# HumFlex3_lower.net
KiCad netlist of a schematic drawn in Altium Designer
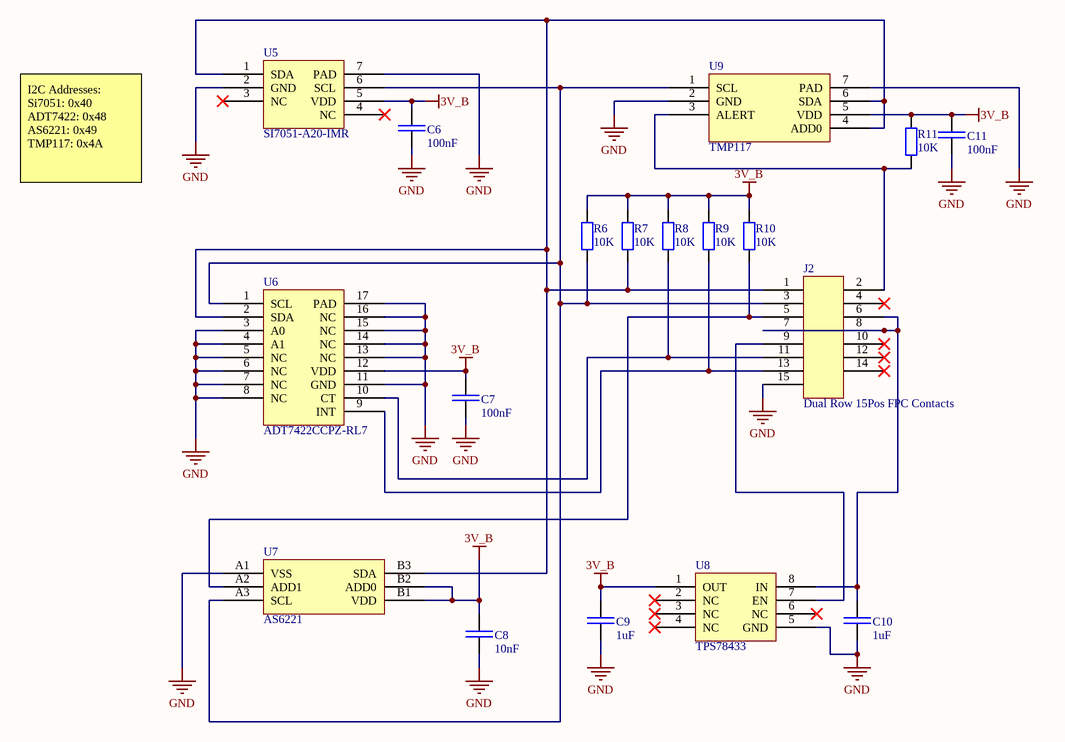
[diagram p0: HumFlex3_lower.SchDoc]

(export (version "E")
  (design (tool "Eeschema 10.0.6"))
  (components
    (comp (ref "C6")
      (value "100nF")
      (footprint "CAP_SM0603_YAGEOCC2_N")
      (description "CAP 100nF SM0603 X7R 50V YAGEO CC2")
      (fields
        (field (name "MANUFACTURER") "Yageo")
        (field (name "MANUFACTURER PART NUMBER") "CC0603KRX7R9BB104")
      )
      (libsource (lib "symbols") (part "CC0603KRX7R9BB104"))
    )
    (comp (ref "C7")
      (value "100nF")
      (footprint "CAP_SM0603_YAGEOCC2_N")
      (description "CAP 100nF SM0603 X7R 50V YAGEO CC2")
      (fields
        (field (name "MANUFACTURER") "Yageo")
        (field (name "MANUFACTURER PART NUMBER") "CC0603KRX7R9BB104")
      )
      (libsource (lib "symbols") (part "CC0603KRX7R9BB104"))
    )
    (comp (ref "C8")
      (value "10nF")
      (footprint "CAP_SM0402_YAGEOCC2_N")
      (description "CAP 10nF SM0402 X7R 50V YAGEO CC2")
      (fields
        (field (name "MANUFACTURER") "Yageo")
        (field (name "MANUFACTURER PART NUMBER") "CC0603KRX7R9BB103")
      )
      (libsource (lib "symbols") (part "CC0402KRX7R9BB103"))
    )
    (comp (ref "C9")
      (value "1uF")
      (footprint "CAP_SM0805_YAGEOCC2_N")
      (description "CAP 1uF SM0805 X7R 25V YAGEO CC2")
      (fields
        (field (name "MANUFACTURER") "Yageo")
        (field (name "MANUFACTURER PART NUMBER") "CC0805KKX7R8BB105")
      )
      (libsource (lib "symbols") (part "CC0805KKX7R8BB105"))
    )
    (comp (ref "C10")
      (value "1uF")
      (footprint "CAP_SM0805_YAGEOCC2_N")
      (description "CAP 1uF SM0805 X7R 25V YAGEO CC2")
      (fields
        (field (name "MANUFACTURER") "Yageo")
        (field (name "MANUFACTURER PART NUMBER") "CC0805KKX7R8BB105")
      )
      (libsource (lib "symbols") (part "CC0805KKX7R8BB105"))
    )
    (comp (ref "C11")
      (value "100nF")
      (footprint "CAP_SM0603_YAGEOCC2_N")
      (description "CAP 100nF SM0603 X7R 50V YAGEO CC2")
      (fields
        (field (name "MANUFACTURER") "Yageo")
        (field (name "MANUFACTURER PART NUMBER") "CC0603KRX7R9BB104")
      )
      (libsource (lib "symbols") (part "CC0603KRX7R9BB104"))
    )
    (comp (ref "J2")
      (value "Dual Row 15Pos FPC Contacts")
      (footprint "AYF331535_FPC")
      (libsource (lib "symbols") (part "FPC_Contacts_15_DualRow"))
    )
    (comp (ref "R6")
      (value "10K")
      (footprint "RES_SM0603_YAGEORC_N")
      (description "RES 10K SM0603 YAGEO RC_L")
      (fields
        (field (name "MANUFACTURER") "Yageo")
        (field (name "MANUFACTURER PART NUMBER") "RC0603FR-0710KL")
      )
      (libsource (lib "symbols") (part "RC0603FR-0710KL"))
    )
    (comp (ref "R7")
      (value "10K")
      (footprint "RES_SM0603_YAGEORC_N")
      (description "RES 10K SM0603 YAGEO RC_L")
      (fields
        (field (name "MANUFACTURER") "Yageo")
        (field (name "MANUFACTURER PART NUMBER") "RC0603FR-0710KL")
      )
      (libsource (lib "symbols") (part "RC0603FR-0710KL"))
    )
    (comp (ref "R8")
      (value "10K")
      (footprint "RES_SM0603_YAGEORC_N")
      (description "RES 10K SM0603 YAGEO RC_L")
      (fields
        (field (name "MANUFACTURER") "Yageo")
        (field (name "MANUFACTURER PART NUMBER") "RC0603FR-0710KL")
      )
      (libsource (lib "symbols") (part "RC0603FR-0710KL"))
    )
    (comp (ref "R9")
      (value "10K")
      (footprint "RES_SM0603_YAGEORC_N")
      (description "RES 10K SM0603 YAGEO RC_L")
      (fields
        (field (name "MANUFACTURER") "Yageo")
        (field (name "MANUFACTURER PART NUMBER") "RC0603FR-0710KL")
      )
      (libsource (lib "symbols") (part "RC0603FR-0710KL"))
    )
    (comp (ref "R10")
      (value "10K")
      (footprint "RES_SM0603_YAGEORC_N")
      (description "RES 10K SM0603 YAGEO RC_L")
      (fields
        (field (name "MANUFACTURER") "Yageo")
        (field (name "MANUFACTURER PART NUMBER") "RC0603FR-0710KL")
      )
      (libsource (lib "symbols") (part "RC0603FR-0710KL"))
    )
    (comp (ref "R11")
      (value "10K")
      (footprint "RES_SM0603_YAGEORC_N")
      (description "RES 10K SM0603 YAGEO RC_L")
      (fields
        (field (name "MANUFACTURER") "Yageo")
        (field (name "MANUFACTURER PART NUMBER") "RC0603FR-0710KL")
      )
      (libsource (lib "symbols") (part "RC0603FR-0710KL"))
    )
    (comp (ref "U5")
      (value "SI7051-A20-IMR")
      (footprint "SI7050/1/2/3/4/5")
      (description "Si7051-A20 Temperature Sensor ±0.1°C maximum accuracy, Digital I2C, -40°C ~ 125°C 14b 6-DFN (3x3)")
      (libsource (lib "symbols") (part "SI7051-A20-IMR"))
    )
    (comp (ref "U6")
      (value "ADT7422CCPZ-RL7")
      (footprint "ADT7422_QFN")
      (libsource (lib "symbols") (part "ADT7422CCPZ-RL7"))
    )
    (comp (ref "U7")
      (value "AS6221")
      (footprint "AS6221_BGA")
      (description "AS6221 Temperature Sensor Digital -40°C ~ 125°C 16b 6-WLCSP (1.5x1.03)")
      (libsource (lib "symbols") (part "AS6221-AWLT-S"))
    )
    (comp (ref "U8")
      (value "TPS78433")
      (footprint "TPS784xxxQDRBRQ1_SON")
      (libsource (lib "symbols") (part "TPS78433QWDRBRQ1"))
    )
    (comp (ref "U9")
      (value "TMP117")
      (footprint "TMP117(N/M)AIDRV_WSON")
      (description "TMP117 High-Accuracy, Low-Power, Digital Temperature Sensor, -55°C bis 150°C, 16b 6-WSON (2x2)")
      (libsource (lib "symbols") (part "TMP117NAIDRVR"))
    )
  )
  (nets
    (net (code "1") (name "3V_B") (class "Default")
      (node (ref "C11") (pin "2") (pintype "passive"))
      (node (ref "C6") (pin "2") (pintype "passive"))
      (node (ref "C7") (pin "2") (pintype "passive"))
      (node (ref "C8") (pin "1") (pintype "passive"))
      (node (ref "C9") (pin "2") (pintype "passive"))
      (node (ref "R10") (pin "2") (pintype "passive"))
      (node (ref "R11") (pin "2") (pintype "passive"))
      (node (ref "R6") (pin "2") (pintype "passive"))
      (node (ref "R7") (pin "2") (pintype "passive"))
      (node (ref "R8") (pin "2") (pintype "passive"))
      (node (ref "R9") (pin "2") (pintype "passive"))
      (node (ref "U5") (pin "5") (pinfunction "VDD_5") (pintype "passive"))
      (node (ref "U6") (pin "12") (pinfunction "VDD_12") (pintype "passive"))
      (node (ref "U7") (pin "B1") (pinfunction "VDD_B1") (pintype "passive"))
      (node (ref "U7") (pin "B2") (pinfunction "ADD0_B2") (pintype "passive"))
      (node (ref "U8") (pin "1") (pinfunction "OUT_1") (pintype "passive"))
      (node (ref "U9") (pin "5") (pinfunction "VDD_5") (pintype "passive"))
    )
    (net (code "2") (name "GND") (class "Default")
      (node (ref "C10") (pin "1") (pintype "passive"))
      (node (ref "C11") (pin "1") (pintype "passive"))
      (node (ref "C6") (pin "1") (pintype "passive"))
      (node (ref "C7") (pin "1") (pintype "passive"))
      (node (ref "C8") (pin "2") (pintype "passive"))
      (node (ref "C9") (pin "1") (pintype "passive"))
      (node (ref "J2") (pin "15") (pintype "passive"))
      (node (ref "U5") (pin "2") (pinfunction "GND_2") (pintype "passive"))
      (node (ref "U5") (pin "7") (pinfunction "PAD_7") (pintype "passive"))
      (node (ref "U6") (pin "11") (pinfunction "GND_11") (pintype "passive"))
      (node (ref "U6") (pin "13") (pinfunction "NC_13") (pintype "passive"))
      (node (ref "U6") (pin "14") (pinfunction "NC_14") (pintype "passive"))
      (node (ref "U6") (pin "15") (pinfunction "NC_15") (pintype "passive"))
      (node (ref "U6") (pin "16") (pinfunction "NC_16") (pintype "passive"))
      (node (ref "U6") (pin "17") (pinfunction "PAD_17") (pintype "passive"))
      (node (ref "U6") (pin "3") (pinfunction "A0_3") (pintype "passive"))
      (node (ref "U6") (pin "4") (pinfunction "A1_4") (pintype "passive"))
      (node (ref "U6") (pin "5") (pinfunction "NC_5") (pintype "passive"))
      (node (ref "U6") (pin "6") (pinfunction "NC_6") (pintype "passive"))
      (node (ref "U6") (pin "7") (pinfunction "NC_7") (pintype "passive"))
      (node (ref "U6") (pin "8") (pinfunction "NC_8") (pintype "passive"))
      (node (ref "U7") (pin "A1") (pinfunction "VSS_A1") (pintype "passive"))
      (node (ref "U8") (pin "5") (pinfunction "GND_5") (pintype "passive"))
      (node (ref "U9") (pin "2") (pinfunction "GND_2") (pintype "passive"))
      (node (ref "U9") (pin "7") (pinfunction "PAD_7") (pintype "passive"))
    )
    (net (code "3") (name "Net-(U5-SCL)") (class "Default")
      (node (ref "J2") (pin "3") (pintype "passive"))
      (node (ref "R6") (pin "1") (pintype "passive"))
      (node (ref "U5") (pin "6") (pinfunction "SCL_6") (pintype "passive"))
      (node (ref "U6") (pin "1") (pinfunction "SCL_1") (pintype "passive"))
      (node (ref "U7") (pin "A3") (pinfunction "SCL_A3") (pintype "passive"))
      (node (ref "U9") (pin "1") (pinfunction "SCL_1") (pintype "passive"))
    )
    (net (code "4") (name "Net-(U5-SDA)") (class "Default")
      (node (ref "J2") (pin "1") (pintype "passive"))
      (node (ref "R7") (pin "1") (pintype "passive"))
      (node (ref "U5") (pin "1") (pinfunction "SDA_1") (pintype "passive"))
      (node (ref "U6") (pin "2") (pinfunction "SDA_2") (pintype "passive"))
      (node (ref "U7") (pin "B3") (pinfunction "SDA_B3") (pintype "passive"))
      (node (ref "U9") (pin "4") (pinfunction "ADD0_4") (pintype "passive"))
      (node (ref "U9") (pin "6") (pinfunction "SDA_6") (pintype "passive"))
    )
    (net (code "5") (name "Net-(U6-CT)") (class "Default")
      (node (ref "J2") (pin "11") (pintype "passive"))
      (node (ref "R8") (pin "1") (pintype "passive"))
      (node (ref "U6") (pin "10") (pinfunction "CT_10") (pintype "passive"))
    )
    (net (code "6") (name "Net-(U6-INT)") (class "Default")
      (node (ref "J2") (pin "13") (pintype "passive"))
      (node (ref "R9") (pin "1") (pintype "passive"))
      (node (ref "U6") (pin "9") (pinfunction "INT_9") (pintype "passive"))
    )
    (net (code "7") (name "Net-(U7-ADD1)") (class "Default")
      (node (ref "J2") (pin "5") (pintype "passive"))
      (node (ref "R10") (pin "1") (pintype "passive"))
      (node (ref "U7") (pin "A2") (pinfunction "ADD1_A2") (pintype "passive"))
    )
    (net (code "8") (name "Net-(U8-EN)") (class "Default")
      (node (ref "J2") (pin "9") (pintype "passive"))
      (node (ref "U8") (pin "7") (pinfunction "EN_7") (pintype "passive"))
    )
    (net (code "9") (name "Net-(U8-IN)") (class "Default")
      (node (ref "C10") (pin "2") (pintype "passive"))
      (node (ref "J2") (pin "6") (pintype "passive"))
      (node (ref "J2") (pin "7") (pintype "passive"))
      (node (ref "J2") (pin "8") (pintype "passive"))
      (node (ref "U8") (pin "8") (pinfunction "IN_8") (pintype "passive"))
    )
    (net (code "10") (name "Net-(U9-ALERT)") (class "Default")
      (node (ref "J2") (pin "2") (pintype "passive"))
      (node (ref "R11") (pin "1") (pintype "passive"))
      (node (ref "U9") (pin "3") (pinfunction "ALERT_3") (pintype "passive"))
    )
    (net (code "11") (name "unconnected-(J2-Pad4)") (class "Default")
      (node (ref "J2") (pin "4") (pintype "passive+no_connect"))
    )
    (net (code "12") (name "unconnected-(J2-Pad10)") (class "Default")
      (node (ref "J2") (pin "10") (pintype "passive+no_connect"))
    )
    (net (code "13") (name "unconnected-(J2-Pad12)") (class "Default")
      (node (ref "J2") (pin "12") (pintype "passive+no_connect"))
    )
    (net (code "14") (name "unconnected-(J2-Pad14)") (class "Default")
      (node (ref "J2") (pin "14") (pintype "passive+no_connect"))
    )
    (net (code "15") (name "unconnected-(U5-NC-Pad3)") (class "Default")
      (node (ref "U5") (pin "3") (pinfunction "NC_3") (pintype "passive+no_connect"))
    )
    (net (code "16") (name "unconnected-(U5-NC-Pad4)") (class "Default")
      (node (ref "U5") (pin "4") (pinfunction "NC_4") (pintype "passive+no_connect"))
    )
    (net (code "17") (name "unconnected-(U8-NC-Pad2)") (class "Default")
      (node (ref "U8") (pin "2") (pinfunction "NC_2") (pintype "passive+no_connect"))
    )
    (net (code "18") (name "unconnected-(U8-NC-Pad3)") (class "Default")
      (node (ref "U8") (pin "3") (pinfunction "NC_3") (pintype "passive+no_connect"))
    )
    (net (code "19") (name "unconnected-(U8-NC-Pad4)") (class "Default")
      (node (ref "U8") (pin "4") (pinfunction "NC_4") (pintype "passive+no_connect"))
    )
    (net (code "20") (name "unconnected-(U8-NC-Pad6)") (class "Default")
      (node (ref "U8") (pin "6") (pinfunction "NC_6") (pintype "passive+no_connect"))
    )
  )
)
